# main.net
KiCad netlist of a schematic drawn in EAGLE
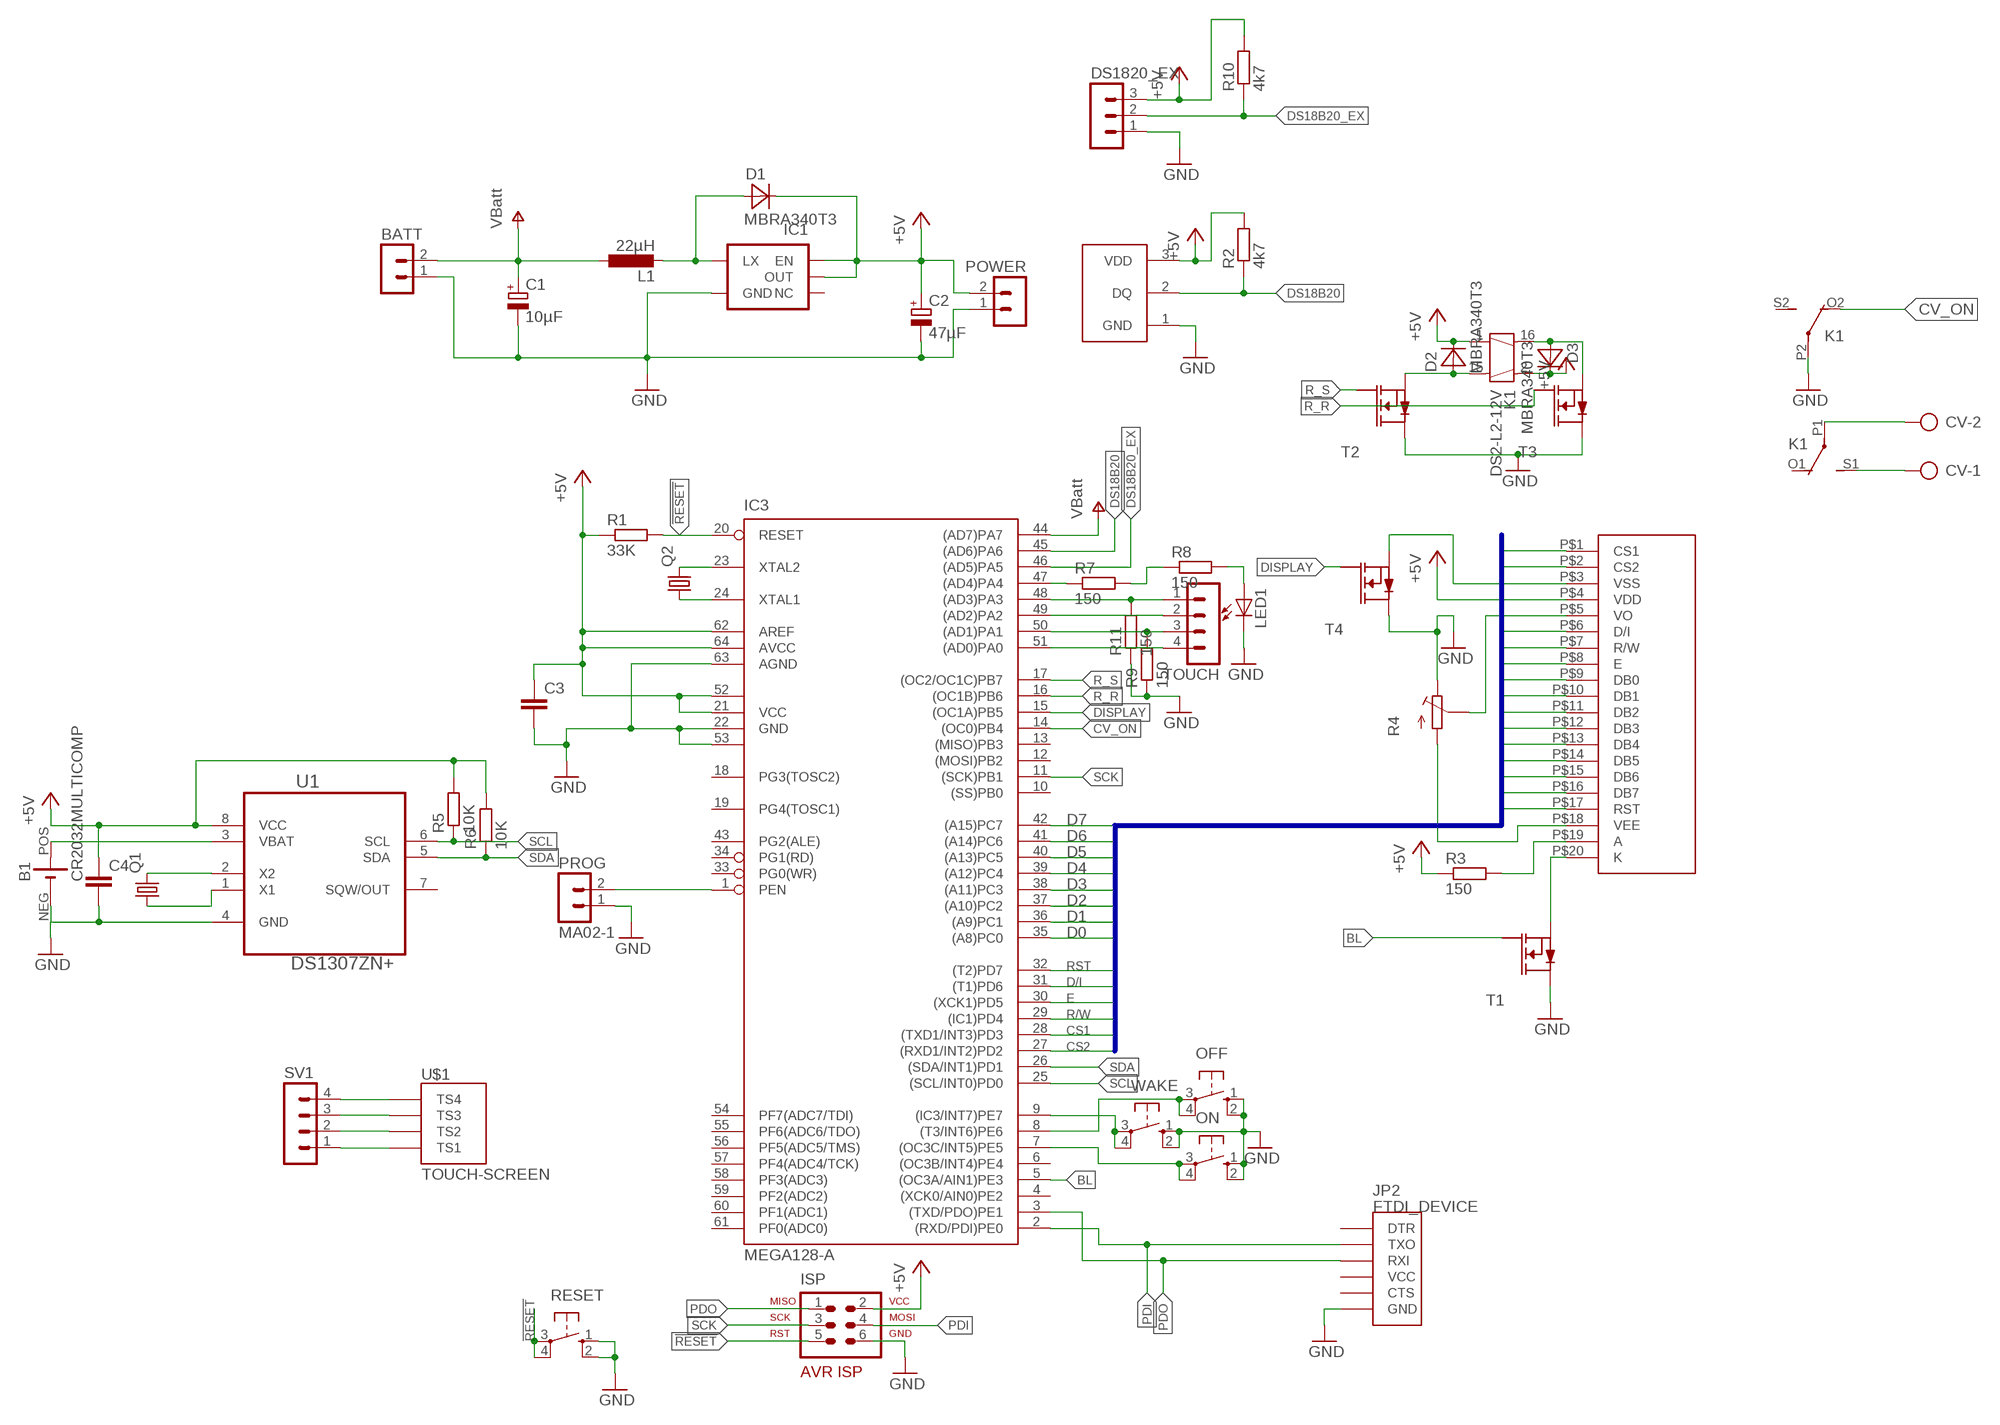
[diagram p0: schematic, sheet 1]

(export (version "E")
  (design (tool "Eeschema 10.0.6"))
  (components
    (comp (ref "B1")
      (value "CR2032MULTICOMP")
      (footprint "eagle-import:CR2032")
      (libsource (lib "eagle-import") (part "CR2032MULTICOMP"))
    )
    (comp (ref "BATT")
      (value "MA02-1")
      (footprint "eagle-import:MA02-1")
      (libsource (lib "eagle-import") (part "MA02-1"))
    )
    (comp (ref "C1")
      (value "10µF")
      (footprint "eagle-import:PANASONIC_D")
      (libsource (lib "eagle-import") (part "CPOL-EUD"))
    )
    (comp (ref "C2")
      (value "47µF")
      (footprint "eagle-import:PANASONIC_D")
      (libsource (lib "eagle-import") (part "CPOL-EUD"))
    )
    (comp (ref "C3")
      (value "C-EUC0805")
      (footprint "eagle-import:C0805")
      (libsource (lib "eagle-import") (part "C-EUC0805"))
    )
    (comp (ref "C4")
      (value "C-EUC0805")
      (footprint "eagle-import:C0805")
      (libsource (lib "eagle-import") (part "C-EUC0805"))
    )
    (comp (ref "CV")
      (value "AK300/2")
      (footprint "eagle-import:AK300_2")
      (libsource (lib "eagle-import") (part "AK300/2"))
    )
    (comp (ref "D1")
      (value "MBRA340T3")
      (footprint "eagle-import:SMA")
      (libsource (lib "eagle-import") (part "MBRA340T3"))
    )
    (comp (ref "D2")
      (value "MBRA340T3")
      (footprint "eagle-import:SMA")
      (libsource (lib "eagle-import") (part "MBRA340T3"))
    )
    (comp (ref "D3")
      (value "MBRA340T3")
      (footprint "eagle-import:SMA")
      (libsource (lib "eagle-import") (part "MBRA340T3"))
    )
    (comp (ref "DS1820")
      (value "DS18B20")
      (footprint "eagle-import:TO92")
      (libsource (lib "eagle-import") (part "DS18B20"))
    )
    (comp (ref "DS1820_EX")
      (value "MA03-1")
      (footprint "eagle-import:MA03-1")
      (libsource (lib "eagle-import") (part "MA03-1"))
    )
    (comp (ref "IC1")
      (value "V_REG_NCP1400SOT23-5")
      (footprint "eagle-import:SOT23-5")
      (libsource (lib "eagle-import") (part "V_REG_NCP1400SOT23-5"))
    )
    (comp (ref "IC3")
      (value "MEGA128-A")
      (footprint "eagle-import:TQFP64")
      (libsource (lib "eagle-import") (part "MEGA128-A"))
    )
    (comp (ref "ISP")
      (value "AVR-ISP-6HORZ")
      (footprint "eagle-import:AVR-ISP-6R")
      (libsource (lib "eagle-import") (part "AVR-ISP-6HORZ"))
    )
    (comp (ref "JP2")
      (value "FTDI_DEVICE")
      (footprint "eagle-import:FTDI_DEVICE_SIDE")
      (libsource (lib "eagle-import") (part "FTDI_DEVICE"))
    )
    (comp (ref "K1")
      (value "DS2-L2-12V")
      (footprint "eagle-import:DS2E-L2")
      (libsource (lib "eagle-import") (part "DS2-L2-12V"))
    )
    (comp (ref "L1")
      (value "22µH")
      (footprint "eagle-import:L2012C")
      (libsource (lib "eagle-import") (part "L-EUL2012C"))
    )
    (comp (ref "LED1")
      (value "LEDSML1206")
      (footprint "eagle-import:SML1206")
      (libsource (lib "eagle-import") (part "LEDSML1206"))
    )
    (comp (ref "OFF")
      (value "10-XX")
      (footprint "eagle-import:B3F-10XX")
      (fields (field (name "MPN") "B3F-1000"))
      (libsource (lib "eagle-import") (part "10-XX"))
    )
    (comp (ref "ON")
      (value "10-XX")
      (footprint "eagle-import:B3F-10XX")
      (fields
        (field (name "MPN") "B3F-1000")
        (field (name "MPN_1") "B3F-1000")
        (field (name "OC_FARNELL") "176432")
        (field (name "OC_NEWARK") "36M3542")
      )
      (libsource (lib "eagle-import") (part "10-XX"))
    )
    (comp (ref "POWER")
      (value "MA02-1")
      (footprint "eagle-import:MA02-1")
      (libsource (lib "eagle-import") (part "MA02-1"))
    )
    (comp (ref "PROG")
      (value "MA02-1")
      (footprint "eagle-import:MA02-1")
      (libsource (lib "eagle-import") (part "MA02-1"))
    )
    (comp (ref "Q1")
      (value "CRYSTALTC26V")
      (footprint "eagle-import:TC26V")
      (libsource (lib "eagle-import") (part "CRYSTALTC26V"))
    )
    (comp (ref "Q2")
      (value "CRYSTALSM49")
      (footprint "eagle-import:SM49")
      (libsource (lib "eagle-import") (part "CRYSTALSM49"))
    )
    (comp (ref "R1")
      (value "33K")
      (footprint "eagle-import:R0805")
      (libsource (lib "eagle-import") (part "R-EU_R0805"))
    )
    (comp (ref "R2")
      (value "4k7")
      (footprint "eagle-import:R0805")
      (libsource (lib "eagle-import") (part "R-EU_R0805"))
    )
    (comp (ref "R3")
      (value "150")
      (footprint "eagle-import:R0805")
      (libsource (lib "eagle-import") (part "R-EU_R0805"))
    )
    (comp (ref "R4")
      (value "TRIM")
      (footprint "eagle-import:TRIM")
      (libsource (lib "eagle-import") (part "TRIM"))
    )
    (comp (ref "R5")
      (value "10K")
      (footprint "eagle-import:R0805")
      (libsource (lib "eagle-import") (part "R-EU_R0805"))
    )
    (comp (ref "R6")
      (value "10K")
      (footprint "eagle-import:R0805")
      (libsource (lib "eagle-import") (part "R-EU_R0805"))
    )
    (comp (ref "R7")
      (value "150")
      (footprint "eagle-import:R0805")
      (libsource (lib "eagle-import") (part "R-EU_R0805"))
    )
    (comp (ref "R8")
      (value "150")
      (footprint "eagle-import:R0805")
      (libsource (lib "eagle-import") (part "R-EU_R0805"))
    )
    (comp (ref "R9")
      (value "150")
      (footprint "eagle-import:R0805")
      (libsource (lib "eagle-import") (part "R-EU_R0805"))
    )
    (comp (ref "R10")
      (value "4k7")
      (footprint "eagle-import:R0805")
      (libsource (lib "eagle-import") (part "R-EU_R0805"))
    )
    (comp (ref "R11")
      (value "150")
      (footprint "eagle-import:R0805")
      (libsource (lib "eagle-import") (part "R-EU_R0805"))
    )
    (comp (ref "RESET")
      (value "10-XX")
      (footprint "eagle-import:B3F-10XX")
      (fields (field (name "MPN") "B3F-1000"))
      (libsource (lib "eagle-import") (part "10-XX"))
    )
    (comp (ref "SV1")
      (value "MA04-1")
      (footprint "eagle-import:MA04-1")
      (libsource (lib "eagle-import") (part "MA04-1"))
    )
    (comp (ref "T1")
      (value "IRLML2502PBF")
      (footprint "eagle-import:SOT23")
      (libsource (lib "eagle-import") (part "IRLML2502PBF"))
    )
    (comp (ref "T2")
      (value "IRLML2502PBF")
      (footprint "eagle-import:SOT23")
      (libsource (lib "eagle-import") (part "IRLML2502PBF"))
    )
    (comp (ref "T3")
      (value "IRLML2502PBF")
      (footprint "eagle-import:SOT23")
      (libsource (lib "eagle-import") (part "IRLML2502PBF"))
    )
    (comp (ref "T4")
      (value "IRLML2502PBF")
      (footprint "eagle-import:SOT23")
      (libsource (lib "eagle-import") (part "IRLML2502PBF"))
    )
    (comp (ref "TOUCH")
      (value "MA04-1")
      (footprint "eagle-import:MA04-1")
      (libsource (lib "eagle-import") (part "MA04-1"))
    )
    (comp (ref "U$1")
      (value "TOUCH-SCREEN")
      (footprint "eagle-import:TOUCH-SCREEN")
      (libsource (lib "eagle-import") (part "TOUCH-SCREEN"))
    )
    (comp (ref "U$2")
      (value "GLCD_LEDSEE")
      (footprint "eagle-import:GLCD_LEDSEE")
      (libsource (lib "eagle-import") (part "GLCD_LEDSEE"))
    )
    (comp (ref "U1")
      (value "DS1307ZN+")
      (footprint "eagle-import:SOIC127P600X175-8N")
      (libsource (lib "eagle-import") (part "DS1307ZN+"))
    )
    (comp (ref "WAKE")
      (value "10-XX")
      (footprint "eagle-import:B3F-10XX")
      (fields (field (name "MPN") "B3F-1000"))
      (libsource (lib "eagle-import") (part "10-XX"))
    )
  )
  (nets
    (net (code "1") (name "+5V") (class "Default")
      (node (ref "C2") (pin "+") (pinfunction "+_+") (pintype "passive"))
      (node (ref "C3") (pin "1") (pinfunction "1_1") (pintype "passive"))
      (node (ref "C4") (pin "1") (pinfunction "1_1") (pintype "passive"))
      (node (ref "D1") (pin "C") (pinfunction "C_C") (pintype "passive"))
      (node (ref "D2") (pin "C") (pinfunction "C_C") (pintype "passive"))
      (node (ref "D3") (pin "C") (pinfunction "C_C") (pintype "passive"))
      (node (ref "DS1820") (pin "3") (pinfunction "VDD_3") (pintype "bidirectional"))
      (node (ref "DS1820_EX") (pin "3") (pinfunction "3_3") (pintype "passive"))
      (node (ref "IC1") (pin "1") (pinfunction "EN_1") (pintype "input"))
      (node (ref "IC1") (pin "2") (pinfunction "OUT_2") (pintype "passive"))
      (node (ref "IC3") (pin "21") (pinfunction "VCC_21") (pintype "power_in"))
      (node (ref "IC3") (pin "52") (pinfunction "VCC1_52") (pintype "power_in"))
      (node (ref "IC3") (pin "62") (pinfunction "AREF_62") (pintype "bidirectional"))
      (node (ref "IC3") (pin "64") (pinfunction "AVCC_64") (pintype "bidirectional"))
      (node (ref "ISP") (pin "2") (pinfunction "2_2") (pintype "passive"))
      (node (ref "K1") (pin "1") (pinfunction "2_1") (pintype "passive"))
      (node (ref "K1") (pin "2") (pinfunction "3_2") (pintype "passive"))
      (node (ref "POWER") (pin "2") (pinfunction "4_2") (pintype "passive"))
      (node (ref "R1") (pin "1") (pinfunction "1_1") (pintype "passive"))
      (node (ref "R10") (pin "2") (pinfunction "2_2") (pintype "passive"))
      (node (ref "R2") (pin "2") (pinfunction "2_2") (pintype "passive"))
      (node (ref "R3") (pin "1") (pinfunction "1_1") (pintype "passive"))
      (node (ref "R5") (pin "2") (pinfunction "2_2") (pintype "passive"))
      (node (ref "R6") (pin "2") (pinfunction "2_2") (pintype "passive"))
      (node (ref "U$2") (pin "P$4") (pinfunction "VDD_P$4") (pintype "power_in"))
      (node (ref "U1") (pin "8") (pinfunction "VCC_8") (pintype "power_in"))
    )
    (net (code "2") (name "/CS1") (class "Default")
      (node (ref "IC3") (pin "28") (pinfunction "(TXD1/INT3)PD3_28") (pintype "bidirectional"))
      (node (ref "U$2") (pin "P$1") (pinfunction "CS1_P$1") (pintype "input"))
    )
    (net (code "3") (name "/CS2") (class "Default")
      (node (ref "IC3") (pin "27") (pinfunction "(RXD1/INT2)PD2_27") (pintype "bidirectional"))
      (node (ref "U$2") (pin "P$2") (pinfunction "CS2_P$2") (pintype "input"))
    )
    (net (code "4") (name "/D0") (class "Default")
      (node (ref "IC3") (pin "35") (pinfunction "(A8)PC0_35") (pintype "output"))
      (node (ref "U$2") (pin "P$9") (pinfunction "DB0_P$9") (pintype "bidirectional"))
    )
    (net (code "5") (name "/D1") (class "Default")
      (node (ref "IC3") (pin "36") (pinfunction "(A9)PC1_36") (pintype "output"))
      (node (ref "U$2") (pin "P$10") (pinfunction "DB1_P$10") (pintype "bidirectional"))
    )
    (net (code "6") (name "/D2") (class "Default")
      (node (ref "IC3") (pin "37") (pinfunction "(A10)PC2_37") (pintype "output"))
      (node (ref "U$2") (pin "P$11") (pinfunction "DB2_P$11") (pintype "bidirectional"))
    )
    (net (code "7") (name "/D3") (class "Default")
      (node (ref "IC3") (pin "38") (pinfunction "(A11)PC3_38") (pintype "output"))
      (node (ref "U$2") (pin "P$12") (pinfunction "DB3_P$12") (pintype "bidirectional"))
    )
    (net (code "8") (name "/D4") (class "Default")
      (node (ref "IC3") (pin "39") (pinfunction "(A12)PC4_39") (pintype "output"))
      (node (ref "U$2") (pin "P$13") (pinfunction "DB4_P$13") (pintype "bidirectional"))
    )
    (net (code "9") (name "/D5") (class "Default")
      (node (ref "IC3") (pin "40") (pinfunction "(A13)PC5_40") (pintype "output"))
      (node (ref "U$2") (pin "P$14") (pinfunction "DB5_P$14") (pintype "bidirectional"))
    )
    (net (code "10") (name "/D6") (class "Default")
      (node (ref "IC3") (pin "41") (pinfunction "(A14)PC6_41") (pintype "output"))
      (node (ref "U$2") (pin "P$15") (pinfunction "DB6_P$15") (pintype "bidirectional"))
    )
    (net (code "11") (name "/D7") (class "Default")
      (node (ref "IC3") (pin "42") (pinfunction "(A15)PC7_42") (pintype "output"))
      (node (ref "U$2") (pin "P$16") (pinfunction "DB7_P$16") (pintype "bidirectional"))
    )
    (net (code "12") (name "/D{slash}I") (class "Default")
      (node (ref "IC3") (pin "31") (pinfunction "(T1)PD6_31") (pintype "bidirectional"))
      (node (ref "U$2") (pin "P$6") (pinfunction "D/I_P$6") (pintype "input"))
    )
    (net (code "13") (name "/E") (class "Default")
      (node (ref "IC3") (pin "30") (pinfunction "(XCK1)PD5_30") (pintype "bidirectional"))
      (node (ref "U$2") (pin "P$8") (pinfunction "E_P$8") (pintype "input"))
    )
    (net (code "14") (name "/RST") (class "Default")
      (node (ref "IC3") (pin "32") (pinfunction "(T2)PD7_32") (pintype "bidirectional"))
      (node (ref "U$2") (pin "P$17") (pinfunction "RST_P$17") (pintype "input"))
    )
    (net (code "15") (name "/R{slash}W") (class "Default")
      (node (ref "IC3") (pin "29") (pinfunction "(IC1)PD4_29") (pintype "bidirectional"))
      (node (ref "U$2") (pin "P$7") (pinfunction "R/W_P$7") (pintype "input"))
    )
    (net (code "16") (name "/~{RESET}") (class "Default")
      (node (ref "IC3") (pin "20") (pinfunction "RESET_20") (pintype "input"))
      (node (ref "ISP") (pin "5") (pinfunction "5_5") (pintype "passive"))
      (node (ref "R1") (pin "2") (pinfunction "2_2") (pintype "passive"))
      (node (ref "RESET") (pin "3") (pinfunction "P_3") (pintype "passive"))
      (node (ref "RESET") (pin "4") (pinfunction "P1_4") (pintype "passive"))
    )
    (net (code "17") (name "BL") (class "Default")
      (node (ref "IC3") (pin "5") (pinfunction "(OC3A/AIN1)PE3_5") (pintype "bidirectional"))
      (node (ref "T1") (pin "1") (pinfunction "G_1") (pintype "bidirectional"))
    )
    (net (code "18") (name "CV_ON") (class "Default")
      (node (ref "IC3") (pin "14") (pinfunction "(OC0)PB4_14") (pintype "bidirectional"))
      (node (ref "K1") (pin "O2") (pinfunction "O_O2") (pintype "passive"))
    )
    (net (code "19") (name "DISPLAY") (class "Default")
      (node (ref "IC3") (pin "15") (pinfunction "(OC1A)PB5_15") (pintype "bidirectional"))
      (node (ref "T4") (pin "1") (pinfunction "G_1") (pintype "bidirectional"))
    )
    (net (code "20") (name "DS18B20") (class "Default")
      (node (ref "DS1820") (pin "2") (pinfunction "DQ_2") (pintype "bidirectional"))
      (node (ref "IC3") (pin "45") (pinfunction "(AD6)PA6_45") (pintype "bidirectional"))
      (node (ref "R2") (pin "1") (pinfunction "1_1") (pintype "passive"))
    )
    (net (code "21") (name "DS18B20_EX") (class "Default")
      (node (ref "DS1820_EX") (pin "2") (pinfunction "2_2") (pintype "passive"))
      (node (ref "IC3") (pin "46") (pinfunction "(AD5)PA5_46") (pintype "bidirectional"))
      (node (ref "R10") (pin "1") (pinfunction "1_1") (pintype "passive"))
    )
    (net (code "22") (name "GND") (class "Default")
      (node (ref "B1") (pin "NEG") (pinfunction "-_NEG") (pintype "passive"))
      (node (ref "BATT") (pin "1") (pinfunction "3_1") (pintype "passive"))
      (node (ref "C1") (pin "-") (pinfunction "-_-") (pintype "passive"))
      (node (ref "C2") (pin "-") (pinfunction "-_-") (pintype "passive"))
      (node (ref "C3") (pin "2") (pinfunction "2_2") (pintype "passive"))
      (node (ref "C4") (pin "2") (pinfunction "2_2") (pintype "passive"))
      (node (ref "DS1820") (pin "1") (pinfunction "GND_1") (pintype "bidirectional"))
      (node (ref "DS1820_EX") (pin "1") (pinfunction "1_1") (pintype "passive"))
      (node (ref "IC1") (pin "4") (pinfunction "GND_4") (pintype "input"))
      (node (ref "IC3") (pin "22") (pinfunction "GND_22") (pintype "power_in"))
      (node (ref "IC3") (pin "53") (pinfunction "GND1_53") (pintype "power_in"))
      (node (ref "IC3") (pin "63") (pinfunction "AGND_63") (pintype "bidirectional"))
      (node (ref "ISP") (pin "6") (pinfunction "6_6") (pintype "passive"))
      (node (ref "JP2") (pin "P$6") (pinfunction "GND_P$6") (pintype "bidirectional"))
      (node (ref "K1") (pin "P2") (pinfunction "P_P2") (pintype "passive"))
      (node (ref "LED1") (pin "C") (pinfunction "C_C") (pintype "passive"))
      (node (ref "OFF") (pin "1") (pinfunction "S_1") (pintype "passive"))
      (node (ref "OFF") (pin "2") (pinfunction "S1_2") (pintype "passive"))
      (node (ref "ON") (pin "1") (pinfunction "S_1") (pintype "passive"))
      (node (ref "ON") (pin "2") (pinfunction "S1_2") (pintype "passive"))
      (node (ref "POWER") (pin "1") (pinfunction "3_1") (pintype "passive"))
      (node (ref "PROG") (pin "1") (pinfunction "3_1") (pintype "passive"))
      (node (ref "R11") (pin "1") (pinfunction "1_1") (pintype "passive"))
      (node (ref "R4") (pin "1") (pinfunction "1_1") (pintype "bidirectional"))
      (node (ref "R9") (pin "1") (pinfunction "1_1") (pintype "passive"))
      (node (ref "RESET") (pin "1") (pinfunction "S_1") (pintype "passive"))
      (node (ref "RESET") (pin "2") (pinfunction "S1_2") (pintype "passive"))
      (node (ref "T1") (pin "3") (pinfunction "D_3") (pintype "bidirectional"))
      (node (ref "T2") (pin "3") (pinfunction "D_3") (pintype "bidirectional"))
      (node (ref "T3") (pin "3") (pinfunction "D_3") (pintype "bidirectional"))
      (node (ref "T4") (pin "3") (pinfunction "D_3") (pintype "bidirectional"))
      (node (ref "U1") (pin "4") (pinfunction "GND_4") (pintype "passive"))
      (node (ref "WAKE") (pin "1") (pinfunction "S_1") (pintype "passive"))
      (node (ref "WAKE") (pin "2") (pinfunction "S1_2") (pintype "passive"))
    )
    (net (code "23") (name "Net-(B1-+)") (class "Default")
      (node (ref "B1") (pin "POS") (pinfunction "+_POS") (pintype "passive"))
      (node (ref "U1") (pin "3") (pinfunction "VBAT_3") (pintype "input"))
    )
    (net (code "24") (name "Net-(CVA-KL)") (class "Default")
      (node (ref "CV") (pin "1") (pinfunction "KL_1") (pintype "passive"))
      (node (ref "K1") (pin "S1") (pinfunction "S_S1") (pintype "passive"))
    )
    (net (code "25") (name "Net-(CVB-KL)") (class "Default")
      (node (ref "CV") (pin "2") (pinfunction "KL_2") (pintype "passive"))
      (node (ref "K1") (pin "P1") (pinfunction "P_P1") (pintype "passive"))
    )
    (net (code "26") (name "Net-(IC1-LX)") (class "Default")
      (node (ref "D1") (pin "A") (pinfunction "A_A") (pintype "passive"))
      (node (ref "IC1") (pin "5") (pinfunction "LX_5") (pintype "input"))
      (node (ref "L1") (pin "2") (pinfunction "2_2") (pintype "passive"))
    )
    (net (code "27") (name "Net-(IC3-(AD0)PA0)") (class "Default")
      (node (ref "IC3") (pin "51") (pinfunction "(AD0)PA0_51") (pintype "bidirectional"))
      (node (ref "TOUCH") (pin "4") (pinfunction "4_4") (pintype "passive"))
    )
    (net (code "28") (name "Net-(IC3-(AD1)PA1)") (class "Default")
      (node (ref "IC3") (pin "50") (pinfunction "(AD1)PA1_50") (pintype "bidirectional"))
      (node (ref "R9") (pin "2") (pinfunction "2_2") (pintype "passive"))
      (node (ref "TOUCH") (pin "3") (pinfunction "3_3") (pintype "passive"))
    )
    (net (code "29") (name "Net-(IC3-(AD2)PA2)") (class "Default")
      (node (ref "IC3") (pin "49") (pinfunction "(AD2)PA2_49") (pintype "bidirectional"))
      (node (ref "TOUCH") (pin "2") (pinfunction "2_2") (pintype "passive"))
    )
    (net (code "30") (name "Net-(IC3-(AD3)PA3)") (class "Default")
      (node (ref "IC3") (pin "48") (pinfunction "(AD3)PA3_48") (pintype "bidirectional"))
      (node (ref "R11") (pin "2") (pinfunction "2_2") (pintype "passive"))
      (node (ref "TOUCH") (pin "1") (pinfunction "1_1") (pintype "passive"))
    )
    (net (code "31") (name "Net-(IC3-(AD4)PA4)") (class "Default")
      (node (ref "IC3") (pin "47") (pinfunction "(AD4)PA4_47") (pintype "bidirectional"))
      (node (ref "R7") (pin "1") (pinfunction "1_1") (pintype "passive"))
    )
    (net (code "32") (name "Net-(IC3-(IC3{slash}INT7)PE7)") (class "Default")
      (node (ref "IC3") (pin "9") (pinfunction "(IC3/INT7)PE7_9") (pintype "bidirectional"))
      (node (ref "WAKE") (pin "3") (pinfunction "P_3") (pintype "passive"))
      (node (ref "WAKE") (pin "4") (pinfunction "P1_4") (pintype "passive"))
    )
    (net (code "33") (name "Net-(IC3-(OC3C{slash}INT5)PE5)") (class "Default")
      (node (ref "IC3") (pin "7") (pinfunction "(OC3C/INT5)PE5_7") (pintype "bidirectional"))
      (node (ref "ON") (pin "3") (pinfunction "P_3") (pintype "passive"))
      (node (ref "ON") (pin "4") (pinfunction "P1_4") (pintype "passive"))
    )
    (net (code "34") (name "Net-(IC3-(T3{slash}INT6)PE6)") (class "Default")
      (node (ref "IC3") (pin "8") (pinfunction "(T3/INT6)PE6_8") (pintype "bidirectional"))
      (node (ref "OFF") (pin "3") (pinfunction "P_3") (pintype "passive"))
      (node (ref "OFF") (pin "4") (pinfunction "P1_4") (pintype "passive"))
    )
    (net (code "35") (name "Net-(IC3-PEN)") (class "Default")
      (node (ref "IC3") (pin "1") (pinfunction "PEN_1") (pintype "input"))
      (node (ref "PROG") (pin "2") (pinfunction "4_2") (pintype "passive"))
    )
    (net (code "36") (name "Net-(IC3-XTAL1)") (class "Default")
      (node (ref "IC3") (pin "24") (pinfunction "XTAL1_24") (pintype "bidirectional"))
      (node (ref "Q2") (pin "1") (pinfunction "1_1") (pintype "passive"))
    )
    (net (code "37") (name "Net-(IC3-XTAL2)") (class "Default")
      (node (ref "IC3") (pin "23") (pinfunction "XTAL2_23") (pintype "bidirectional"))
      (node (ref "Q2") (pin "2") (pinfunction "2_2") (pintype "passive"))
    )
    (net (code "38") (name "Net-(K1A-1)") (class "Default")
      (node (ref "D3") (pin "A") (pinfunction "A_A") (pintype "passive"))
      (node (ref "K1") (pin "16") (pinfunction "1_16") (pintype "passive"))
      (node (ref "T3") (pin "2") (pinfunction "S_2") (pintype "bidirectional"))
    )
    (net (code "39") (name "Net-(K1A-4)") (class "Default")
      (node (ref "D2") (pin "A") (pinfunction "A_A") (pintype "passive"))
      (node (ref "K1") (pin "15") (pinfunction "4_15") (pintype "passive"))
      (node (ref "T2") (pin "2") (pinfunction "S_2") (pintype "bidirectional"))
    )
    (net (code "40") (name "Net-(LED1-PadA)") (class "Default")
      (node (ref "LED1") (pin "A") (pinfunction "A_A") (pintype "passive"))
      (node (ref "R8") (pin "2") (pinfunction "2_2") (pintype "passive"))
    )
    (net (code "41") (name "Net-(R4-T)") (class "Default")
      (node (ref "R4") (pin "2") (pinfunction "T_2") (pintype "bidirectional"))
      (node (ref "U$2") (pin "P$5") (pinfunction "VO_P$5") (pintype "bidirectional"))
    )
    (net (code "42") (name "Net-(R7-Pad2)") (class "Default")
      (node (ref "R7") (pin "2") (pinfunction "2_2") (pintype "passive"))
      (node (ref "R8") (pin "1") (pinfunction "1_1") (pintype "passive"))
    )
    (net (code "43") (name "Net-(T1-S)") (class "Default")
      (node (ref "T1") (pin "2") (pinfunction "S_2") (pintype "bidirectional"))
      (node (ref "U$2") (pin "P$20") (pinfunction "K_P$20") (pintype "power_in"))
    )
    (net (code "44") (name "Net-(T4-S)") (class "Default")
      (node (ref "T4") (pin "2") (pinfunction "S_2") (pintype "bidirectional"))
      (node (ref "U$2") (pin "P$3") (pinfunction "VSS_P$3") (pintype "power_in"))
    )
    (net (code "45") (name "Net-(U$1-TS1)") (class "Default")
      (node (ref "SV1") (pin "1") (pinfunction "1_1") (pintype "passive"))
      (node (ref "U$1") (pin "P$4") (pinfunction "TS1_P$4") (pintype "bidirectional"))
    )
    (net (code "46") (name "Net-(U$1-TS2)") (class "Default")
      (node (ref "SV1") (pin "2") (pinfunction "2_2") (pintype "passive"))
      (node (ref "U$1") (pin "P$3") (pinfunction "TS2_P$3") (pintype "bidirectional"))
    )
    (net (code "47") (name "Net-(U$1-TS3)") (class "Default")
      (node (ref "SV1") (pin "3") (pinfunction "3_3") (pintype "passive"))
      (node (ref "U$1") (pin "P$2") (pinfunction "TS3_P$2") (pintype "bidirectional"))
    )
    (net (code "48") (name "Net-(U$1-TS4)") (class "Default")
      (node (ref "SV1") (pin "4") (pinfunction "4_4") (pintype "passive"))
      (node (ref "U$1") (pin "P$1") (pinfunction "TS4_P$1") (pintype "bidirectional"))
    )
    (net (code "49") (name "Net-(U$2-A)") (class "Default")
      (node (ref "R3") (pin "2") (pinfunction "2_2") (pintype "passive"))
      (node (ref "U$2") (pin "P$19") (pinfunction "A_P$19") (pintype "power_in"))
    )
    (net (code "50") (name "Net-(U$2-VEE)") (class "Default")
      (node (ref "R4") (pin "3") (pinfunction "3_3") (pintype "bidirectional"))
      (node (ref "U$2") (pin "P$18") (pinfunction "VEE_P$18") (pintype "bidirectional"))
    )
    (net (code "51") (name "Net-(U1-X1)") (class "Default")
      (node (ref "Q1") (pin "1") (pinfunction "1_1") (pintype "passive"))
      (node (ref "U1") (pin "1") (pinfunction "X1_1") (pintype "input"))
    )
    (net (code "52") (name "Net-(U1-X2)") (class "Default")
      (node (ref "Q1") (pin "2") (pinfunction "2_2") (pintype "passive"))
      (node (ref "U1") (pin "2") (pinfunction "X2_2") (pintype "output"))
    )
    (net (code "53") (name "PDI") (class "Default")
      (node (ref "IC3") (pin "2") (pinfunction "(RXD/PDI)PE0_2") (pintype "bidirectional"))
      (node (ref "ISP") (pin "4") (pinfunction "4_4") (pintype "passive"))
      (node (ref "JP2") (pin "P$2") (pinfunction "TXO_P$2") (pintype "bidirectional"))
    )
    (net (code "54") (name "PDO") (class "Default")
      (node (ref "IC3") (pin "3") (pinfunction "(TXD/PDO)PE1_3") (pintype "bidirectional"))
      (node (ref "ISP") (pin "1") (pinfunction "1_1") (pintype "passive"))
      (node (ref "JP2") (pin "P$3") (pinfunction "RXI_P$3") (pintype "bidirectional"))
    )
    (net (code "55") (name "R_R") (class "Default")
      (node (ref "IC3") (pin "16") (pinfunction "(OC1B)PB6_16") (pintype "bidirectional"))
      (node (ref "T3") (pin "1") (pinfunction "G_1") (pintype "bidirectional"))
    )
    (net (code "56") (name "R_S") (class "Default")
      (node (ref "IC3") (pin "17") (pinfunction "(OC2/OC1C)PB7_17") (pintype "bidirectional"))
      (node (ref "T2") (pin "1") (pinfunction "G_1") (pintype "bidirectional"))
    )
    (net (code "57") (name "SCK") (class "Default")
      (node (ref "IC3") (pin "11") (pinfunction "(SCK)PB1_11") (pintype "bidirectional"))
      (node (ref "ISP") (pin "3") (pinfunction "3_3") (pintype "passive"))
    )
    (net (code "58") (name "SCL") (class "Default")
      (node (ref "IC3") (pin "25") (pinfunction "(SCL/INT0)PD0_25") (pintype "bidirectional"))
      (node (ref "R5") (pin "1") (pinfunction "1_1") (pintype "passive"))
      (node (ref "U1") (pin "6") (pinfunction "SCL_6") (pintype "input"))
    )
    (net (code "59") (name "SDA") (class "Default")
      (node (ref "IC3") (pin "26") (pinfunction "(SDA/INT1)PD1_26") (pintype "bidirectional"))
      (node (ref "R6") (pin "1") (pinfunction "1_1") (pintype "passive"))
      (node (ref "U1") (pin "5") (pinfunction "SDA_5") (pintype "bidirectional"))
    )
    (net (code "60") (name "VBatt") (class "Default")
      (node (ref "BATT") (pin "2") (pinfunction "4_2") (pintype "passive"))
      (node (ref "C1") (pin "+") (pinfunction "+_+") (pintype "passive"))
      (node (ref "IC3") (pin "44") (pinfunction "(AD7)PA7_44") (pintype "bidirectional"))
      (node (ref "L1") (pin "1") (pinfunction "1_1") (pintype "passive"))
    )
    (net (code "61") (name "unconnected-(IC1-NC-Pad3)") (class "Default")
      (node (ref "IC1") (pin "3") (pinfunction "NC_3") (pintype "input"))
    )
    (net (code "62") (name "unconnected-(IC3-(MISO)PB3-Pad13)") (class "Default")
      (node (ref "IC3") (pin "13") (pinfunction "(MISO)PB3_13") (pintype "bidirectional"))
    )
    (net (code "63") (name "unconnected-(IC3-(MOSI)PB2-Pad12)") (class "Default")
      (node (ref "IC3") (pin "12") (pinfunction "(MOSI)PB2_12") (pintype "bidirectional"))
    )
    (net (code "64") (name "unconnected-(IC3-(OC3B{slash}INT4)PE4-Pad6)") (class "Default")
      (node (ref "IC3") (pin "6") (pinfunction "(OC3B/INT4)PE4_6") (pintype "bidirectional"))
    )
    (net (code "65") (name "unconnected-(IC3-(SS)PB0-Pad10)") (class "Default")
      (node (ref "IC3") (pin "10") (pinfunction "(SS)PB0_10") (pintype "bidirectional"))
    )
    (net (code "66") (name "unconnected-(IC3-(XCK0{slash}AIN0)PE2-Pad4)") (class "Default")
      (node (ref "IC3") (pin "4") (pinfunction "(XCK0/AIN0)PE2_4") (pintype "bidirectional"))
    )
    (net (code "67") (name "unconnected-(IC3-PF0(ADC0)-Pad61)") (class "Default")
      (node (ref "IC3") (pin "61") (pinfunction "PF0(ADC0)_61") (pintype "input"))
    )
    (net (code "68") (name "unconnected-(IC3-PF1(ADC1)-Pad60)") (class "Default")
      (node (ref "IC3") (pin "60") (pinfunction "PF1(ADC1)_60") (pintype "input"))
    )
    (net (code "69") (name "unconnected-(IC3-PF2(ADC2)-Pad59)") (class "Default")
      (node (ref "IC3") (pin "59") (pinfunction "PF2(ADC2)_59") (pintype "input"))
    )
    (net (code "70") (name "unconnected-(IC3-PF3(ADC3)-Pad58)") (class "Default")
      (node (ref "IC3") (pin "58") (pinfunction "PF3(ADC3)_58") (pintype "input"))
    )
    (net (code "71") (name "unconnected-(IC3-PF4(ADC4{slash}TCK)-Pad57)") (class "Default")
      (node (ref "IC3") (pin "57") (pinfunction "PF4(ADC4/TCK)_57") (pintype "input"))
    )
    (net (code "72") (name "unconnected-(IC3-PF5(ADC5{slash}TMS)-Pad56)") (class "Default")
      (node (ref "IC3") (pin "56") (pinfunction "PF5(ADC5/TMS)_56") (pintype "input"))
    )
    (net (code "73") (name "unconnected-(IC3-PF6(ADC6{slash}TDO)-Pad55)") (class "Default")
      (node (ref "IC3") (pin "55") (pinfunction "PF6(ADC6/TDO)_55") (pintype "input"))
    )
    (net (code "74") (name "unconnected-(IC3-PF7(ADC7{slash}TDI)-Pad54)") (class "Default")
      (node (ref "IC3") (pin "54") (pinfunction "PF7(ADC7/TDI)_54") (pintype "input"))
    )
    (net (code "75") (name "unconnected-(IC3-PG0(WR)-Pad33)") (class "Default")
      (node (ref "IC3") (pin "33") (pinfunction "PG0(WR)_33") (pintype "bidirectional"))
    )
    (net (code "76") (name "unconnected-(IC3-PG1(RD)-Pad34)") (class "Default")
      (node (ref "IC3") (pin "34") (pinfunction "PG1(RD)_34") (pintype "bidirectional"))
    )
    (net (code "77") (name "unconnected-(IC3-PG2(ALE)-Pad43)") (class "Default")
      (node (ref "IC3") (pin "43") (pinfunction "PG2(ALE)_43") (pintype "bidirectional"))
    )
    (net (code "78") (name "unconnected-(IC3-PG3(TOSC2)-Pad18)") (class "Default")
      (node (ref "IC3") (pin "18") (pinfunction "PG3(TOSC2)_18") (pintype "bidirectional"))
    )
    (net (code "79") (name "unconnected-(IC3-PG4(TOSC1)-Pad19)") (class "Default")
      (node (ref "IC3") (pin "19") (pinfunction "PG4(TOSC1)_19") (pintype "bidirectional"))
    )
    (net (code "80") (name "unconnected-(JP2-CTS-PadP$5)") (class "Default")
      (node (ref "JP2") (pin "P$5") (pinfunction "CTS_P$5") (pintype "bidirectional"))
    )
    (net (code "81") (name "unconnected-(JP2-DTR-PadP$1)") (class "Default")
      (node (ref "JP2") (pin "P$1") (pinfunction "DTR_P$1") (pintype "bidirectional"))
    )
    (net (code "82") (name "unconnected-(JP2-VCC-PadP$4)") (class "Default")
      (node (ref "JP2") (pin "P$4") (pinfunction "VCC_P$4") (pintype "bidirectional"))
    )
    (net (code "83") (name "unconnected-(K1B-O-PadO1)") (class "Default")
      (node (ref "K1") (pin "O1") (pinfunction "O_O1") (pintype "passive"))
    )
    (net (code "84") (name "unconnected-(K1C-S-PadS2)") (class "Default")
      (node (ref "K1") (pin "S2") (pinfunction "S_S2") (pintype "passive"))
    )
    (net (code "85") (name "unconnected-(U1-SQW{slash}OUT-Pad7)") (class "Default")
      (node (ref "U1") (pin "7") (pinfunction "SQW/OUT_7") (pintype "bidirectional"))
    )
  )
)
